# Hatch2023Trophy_1.net
KiCad netlist of a schematic drawn in EAGLE
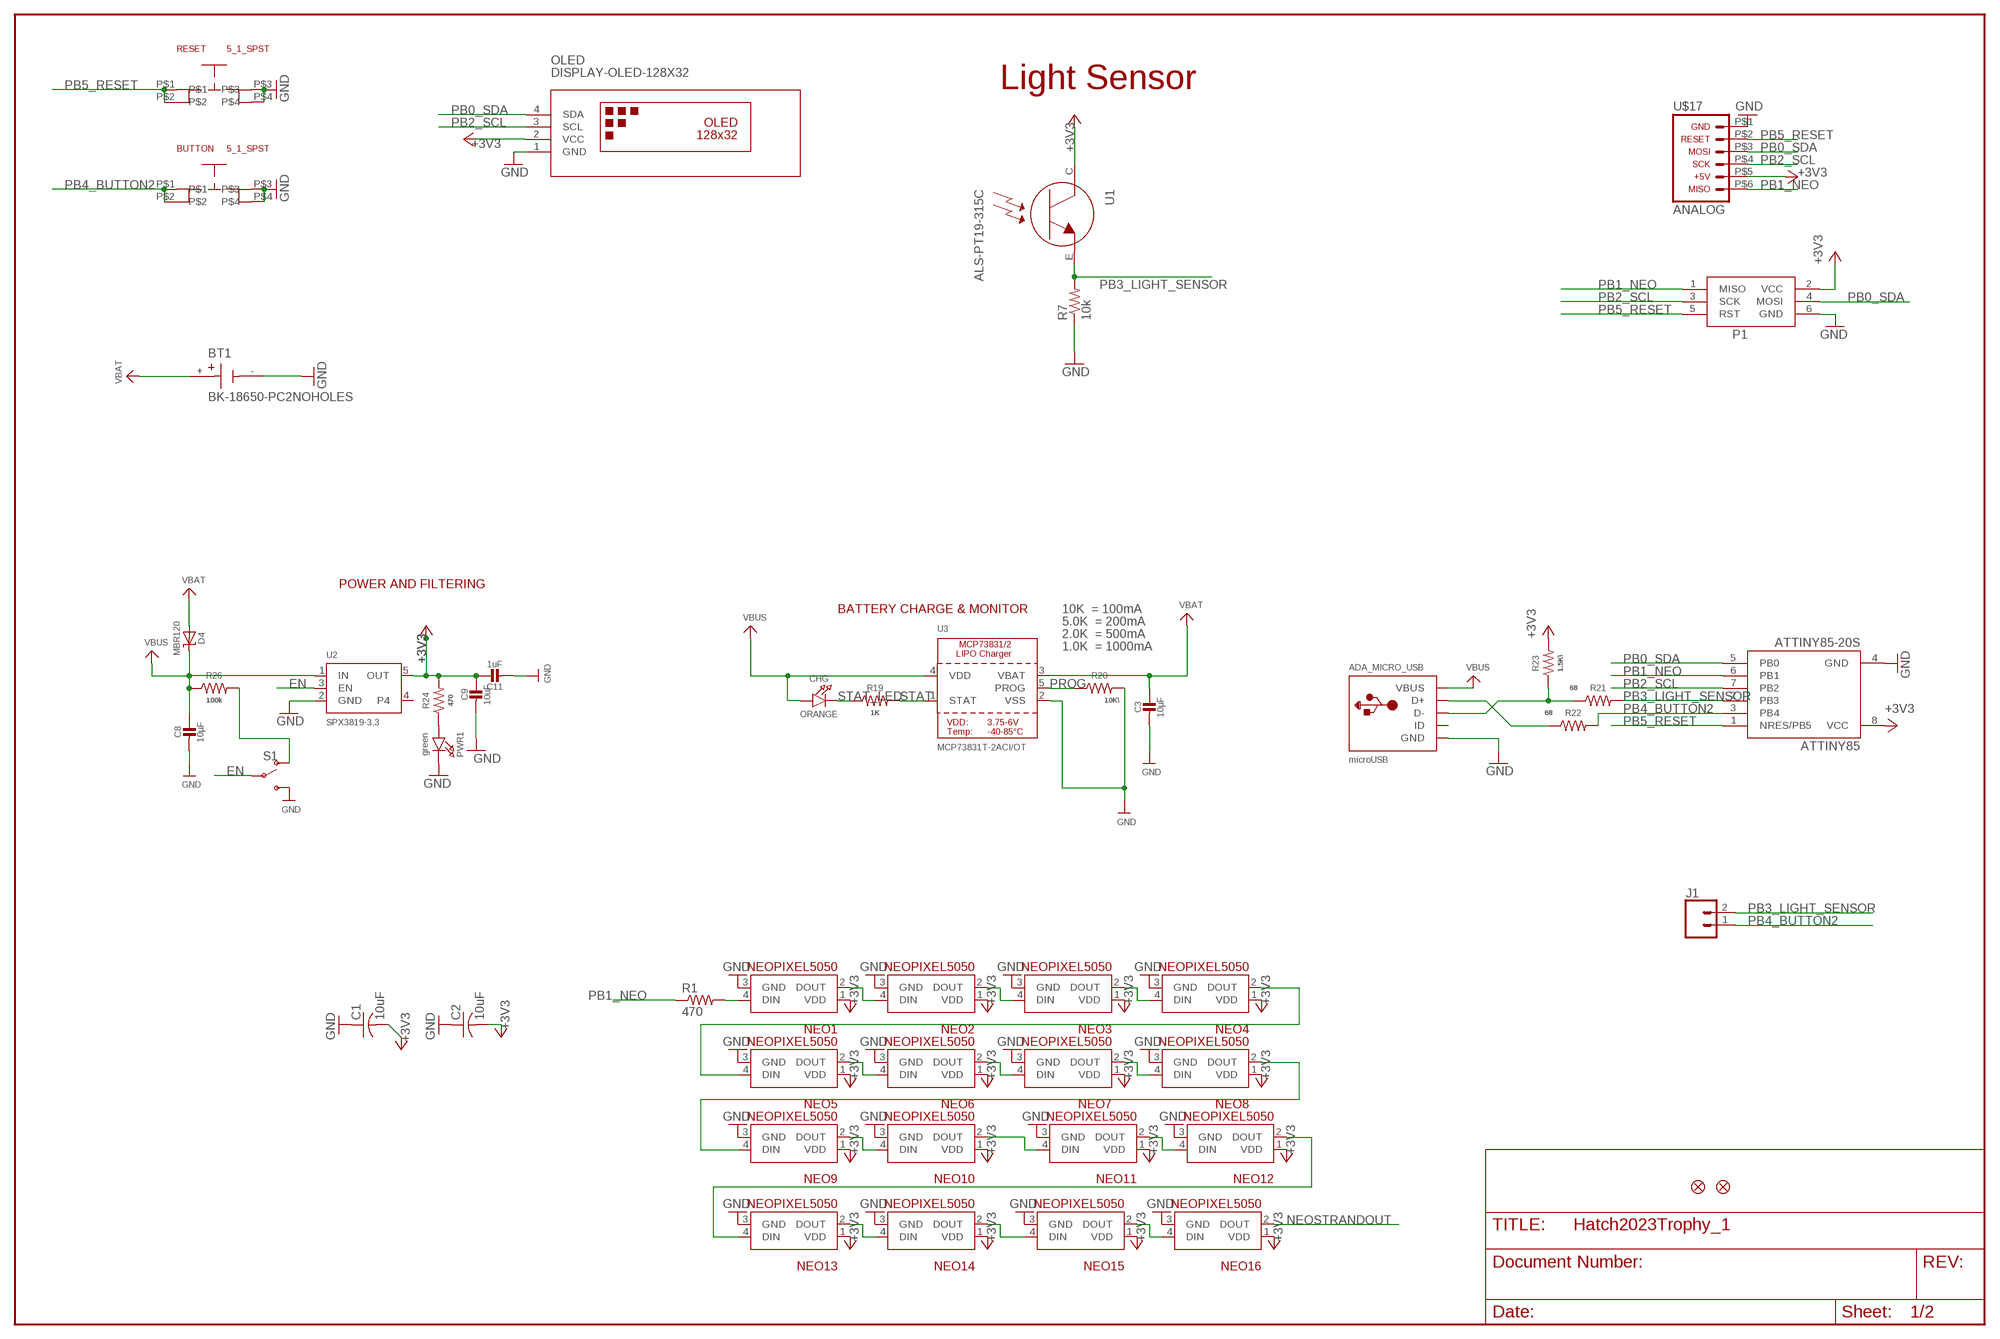
[diagram p0: schematic, sheet 1]

(export (version "E")
  (design (tool "Eeschema 10.0.6"))
  (components
    (comp (ref "ADA_MICRO_USB")
      (value "microUSB")
      (footprint "eagle-import:4UCONN_20329_V2")
      (libsource (lib "eagle-import") (part "USB_MICRO_20329_V2"))
    )
    (comp (ref "ATTINY85")
      (value "ATTINY85-20S")
      (footprint "eagle-import:SOIC8_EIAJ_208MIL")
      (libsource (lib "eagle-import") (part "ATTINY85S-20"))
    )
    (comp (ref "BT1")
      (value "BK-18650-PC2NOHOLES")
      (footprint "eagle-import:BAT_BK-18650-PC2_NOHOLES")
      (libsource (lib "eagle-import") (part "BK-18650-PC2NOHOLES"))
    )
    (comp (ref "BUTTON")
      (value "5_1_SPST")
      (footprint "eagle-import:5_1_SPST")
      (libsource (lib "eagle-import") (part "5_1_SPST"))
    )
    (comp (ref "C1")
      (value "10uF")
      (footprint "eagle-import:C0805")
      (libsource (lib "eagle-import") (part "C-USC0805"))
    )
    (comp (ref "C2")
      (value "10uF")
      (footprint "eagle-import:C0805")
      (libsource (lib "eagle-import") (part "C-USC0805"))
    )
    (comp (ref "C3")
      (value "10µF")
      (footprint "eagle-import:0805-NO@1")
      (libsource (lib "eagle-import") (part "CAP_CERAMIC0805-NOOUTLINE"))
    )
    (comp (ref "C8")
      (value "10µF")
      (footprint "eagle-import:0805-NO@1")
      (libsource (lib "eagle-import") (part "CAP_CERAMIC0805-NOOUTLINE"))
    )
    (comp (ref "C9")
      (value "10uF")
      (footprint "eagle-import:0805-NO@1")
      (libsource (lib "eagle-import") (part "CAP_CERAMIC0805-NOOUTLINE"))
    )
    (comp (ref "C11")
      (value "1uF")
      (footprint "eagle-import:0805-NO@1")
      (libsource (lib "eagle-import") (part "CAP_CERAMIC0805-NOOUTLINE"))
    )
    (comp (ref "CHG")
      (value "ORANGE")
      (footprint "eagle-import:CHIPLED_0805_NOOUTLINE")
      (libsource (lib "eagle-import") (part "LED0805_NOOUTLINE"))
    )
    (comp (ref "D4")
      (value "MBR120")
      (footprint "eagle-import:SOD-123")
      (libsource (lib "eagle-import") (part "DIODE-SCHOTTKYSOD-123"))
    )
    (comp (ref "J1")
      (value "CONN_02")
      (footprint "eagle-import:1X02")
      (libsource (lib "eagle-import") (part "CONN_02"))
    )
    (comp (ref "NEO1")
      (value "NEOPIXEL5050")
      (footprint "eagle-import:NEOPIXEL5050")
      (libsource (lib "eagle-import") (part "NEOPIXEL5050"))
    )
    (comp (ref "NEO2")
      (value "NEOPIXEL5050")
      (footprint "eagle-import:NEOPIXEL5050")
      (libsource (lib "eagle-import") (part "NEOPIXEL5050"))
    )
    (comp (ref "NEO3")
      (value "NEOPIXEL5050")
      (footprint "eagle-import:NEOPIXEL5050")
      (libsource (lib "eagle-import") (part "NEOPIXEL5050"))
    )
    (comp (ref "NEO4")
      (value "NEOPIXEL5050")
      (footprint "eagle-import:NEOPIXEL5050")
      (libsource (lib "eagle-import") (part "NEOPIXEL5050"))
    )
    (comp (ref "NEO5")
      (value "NEOPIXEL5050")
      (footprint "eagle-import:NEOPIXEL5050")
      (libsource (lib "eagle-import") (part "NEOPIXEL5050"))
    )
    (comp (ref "NEO6")
      (value "NEOPIXEL5050")
      (footprint "eagle-import:NEOPIXEL5050")
      (libsource (lib "eagle-import") (part "NEOPIXEL5050"))
    )
    (comp (ref "NEO7")
      (value "NEOPIXEL5050")
      (footprint "eagle-import:NEOPIXEL5050")
      (libsource (lib "eagle-import") (part "NEOPIXEL5050"))
    )
    (comp (ref "NEO8")
      (value "NEOPIXEL5050")
      (footprint "eagle-import:NEOPIXEL5050")
      (libsource (lib "eagle-import") (part "NEOPIXEL5050"))
    )
    (comp (ref "NEO9")
      (value "NEOPIXEL5050")
      (footprint "eagle-import:NEOPIXEL5050")
      (libsource (lib "eagle-import") (part "NEOPIXEL5050"))
    )
    (comp (ref "NEO10")
      (value "NEOPIXEL5050")
      (footprint "eagle-import:NEOPIXEL5050")
      (libsource (lib "eagle-import") (part "NEOPIXEL5050"))
    )
    (comp (ref "NEO11")
      (value "NEOPIXEL5050")
      (footprint "eagle-import:NEOPIXEL5050")
      (libsource (lib "eagle-import") (part "NEOPIXEL5050"))
    )
    (comp (ref "NEO12")
      (value "NEOPIXEL5050")
      (footprint "eagle-import:NEOPIXEL5050")
      (libsource (lib "eagle-import") (part "NEOPIXEL5050"))
    )
    (comp (ref "NEO13")
      (value "NEOPIXEL5050")
      (footprint "eagle-import:NEOPIXEL5050")
      (libsource (lib "eagle-import") (part "NEOPIXEL5050"))
    )
    (comp (ref "NEO14")
      (value "NEOPIXEL5050")
      (footprint "eagle-import:NEOPIXEL5050")
      (libsource (lib "eagle-import") (part "NEOPIXEL5050"))
    )
    (comp (ref "NEO15")
      (value "NEOPIXEL5050")
      (footprint "eagle-import:NEOPIXEL5050")
      (libsource (lib "eagle-import") (part "NEOPIXEL5050"))
    )
    (comp (ref "NEO16")
      (value "NEOPIXEL5050")
      (footprint "eagle-import:NEOPIXEL5050")
      (libsource (lib "eagle-import") (part "NEOPIXEL5050"))
    )
    (comp (ref "OLED")
      (value "DISPLAY-OLED-128X32")
      (footprint "eagle-import:DISPLAY-OLED-128X32")
      (libsource (lib "eagle-import") (part "DISPLAY-OLED-128X32"))
    )
    (comp (ref "P1")
      (value "AVRISP-6")
      (footprint "eagle-import:AVRISP")
      (libsource (lib "eagle-import") (part "AVRISP-6"))
    )
    (comp (ref "PWR1")
      (value "green")
      (footprint "eagle-import:CHIPLED_0805_NOOUTLINE")
      (libsource (lib "eagle-import") (part "LED0805_NOOUTLINE"))
    )
    (comp (ref "R1")
      (value "470")
      (footprint "eagle-import:R0805")
      (libsource (lib "eagle-import") (part "R-US_R0805"))
    )
    (comp (ref "R7")
      (value "10k")
      (footprint "eagle-import:R0805")
      (libsource (lib "eagle-import") (part "R-US_R0805"))
    )
    (comp (ref "R19")
      (value "1K")
      (footprint "eagle-import:R0805")
      (libsource (lib "eagle-import") (part "R-US_R0805"))
    )
    (comp (ref "R20")
      (value "10K\\")
      (footprint "eagle-import:R0805")
      (libsource (lib "eagle-import") (part "R-US_R0805"))
    )
    (comp (ref "R21")
      (value "68")
      (footprint "eagle-import:R0805")
      (libsource (lib "eagle-import") (part "R-US_R0805"))
    )
    (comp (ref "R22")
      (value "68")
      (footprint "eagle-import:R0805")
      (libsource (lib "eagle-import") (part "R-US_R0805"))
    )
    (comp (ref "R23")
      (value "1.5K\\")
      (footprint "eagle-import:R0805")
      (libsource (lib "eagle-import") (part "R-US_R0805"))
    )
    (comp (ref "R24")
      (value "470")
      (footprint "eagle-import:R0805")
      (libsource (lib "eagle-import") (part "R-US_R0805"))
    )
    (comp (ref "R26")
      (value "100k")
      (footprint "eagle-import:R0805")
      (libsource (lib "eagle-import") (part "R-US_R0805"))
    )
    (comp (ref "RESET")
      (value "5_1_SPST")
      (footprint "eagle-import:5_1_SPST")
      (libsource (lib "eagle-import") (part "5_1_SPST"))
    )
    (comp (ref "S1")
      (value "SWITCH-SPDT-SMD-AYZ0202")
      (footprint "eagle-import:SWITCH_DPDT_SMD_AYZ0202")
      (libsource (lib "eagle-import") (part "SWITCH-SPDT-SMD-AYZ0202"))
    )
    (comp (ref "U$17")
      (value "ICSP_FLATSMD_2X3")
      (footprint "eagle-import:CONN-SMD-2X3")
      (libsource (lib "eagle-import") (part "ICSP_FLATSMD_2X3"))
    )
    (comp (ref "U$34")
      (value "FIDUCIAL_1MM")
      (footprint "eagle-import:FIDUCIAL_1MM")
      (libsource (lib "eagle-import") (part "FIDUCIAL_1MM"))
    )
    (comp (ref "U$35")
      (value "FIDUCIAL_1MM")
      (footprint "eagle-import:FIDUCIAL_1MM")
      (libsource (lib "eagle-import") (part "FIDUCIAL_1MM"))
    )
    (comp (ref "U1")
      (value "ALS-PT19-315C")
      (footprint "eagle-import:ALS-PT19-315C")
      (libsource (lib "eagle-import") (part "LIGHT_ALS-PT19-315C"))
    )
    (comp (ref "U2")
      (value "SPX3819-3.3")
      (footprint "eagle-import:SOT23-5")
      (libsource (lib "eagle-import") (part "VREG_SOT23-5"))
    )
    (comp (ref "U3")
      (value "MCP73831T-2ACI/OT")
      (footprint "eagle-import:SOT23-5")
      (libsource (lib "eagle-import") (part "MCP73831/2"))
    )
  )
  (nets
    (net (code "1") (name "+3V3") (class "Default")
      (node (ref "ATTINY85") (pin "8") (pinfunction "VCC_8") (pintype "power_in"))
      (node (ref "C1") (pin "2") (pinfunction "2_2") (pintype "passive"))
      (node (ref "C11") (pin "1") (pinfunction "1_1") (pintype "passive"))
      (node (ref "C2") (pin "2") (pinfunction "2_2") (pintype "passive"))
      (node (ref "C9") (pin "1") (pinfunction "1_1") (pintype "passive"))
      (node (ref "NEO1") (pin "1") (pinfunction "VDD_1") (pintype "bidirectional"))
      (node (ref "NEO10") (pin "1") (pinfunction "VDD_1") (pintype "bidirectional"))
      (node (ref "NEO11") (pin "1") (pinfunction "VDD_1") (pintype "bidirectional"))
      (node (ref "NEO12") (pin "1") (pinfunction "VDD_1") (pintype "bidirectional"))
      (node (ref "NEO13") (pin "1") (pinfunction "VDD_1") (pintype "bidirectional"))
      (node (ref "NEO14") (pin "1") (pinfunction "VDD_1") (pintype "bidirectional"))
      (node (ref "NEO15") (pin "1") (pinfunction "VDD_1") (pintype "bidirectional"))
      (node (ref "NEO16") (pin "1") (pinfunction "VDD_1") (pintype "bidirectional"))
      (node (ref "NEO2") (pin "1") (pinfunction "VDD_1") (pintype "bidirectional"))
      (node (ref "NEO3") (pin "1") (pinfunction "VDD_1") (pintype "bidirectional"))
      (node (ref "NEO4") (pin "1") (pinfunction "VDD_1") (pintype "bidirectional"))
      (node (ref "NEO5") (pin "1") (pinfunction "VDD_1") (pintype "bidirectional"))
      (node (ref "NEO6") (pin "1") (pinfunction "VDD_1") (pintype "bidirectional"))
      (node (ref "NEO7") (pin "1") (pinfunction "VDD_1") (pintype "bidirectional"))
      (node (ref "NEO8") (pin "1") (pinfunction "VDD_1") (pintype "bidirectional"))
      (node (ref "NEO9") (pin "1") (pinfunction "VDD_1") (pintype "bidirectional"))
      (node (ref "OLED") (pin "2") (pinfunction "VCC_2") (pintype "power_in"))
      (node (ref "P1") (pin "2") (pinfunction "VCC_2") (pintype "power_in"))
      (node (ref "R23") (pin "2") (pinfunction "2_2") (pintype "passive"))
      (node (ref "R24") (pin "2") (pinfunction "2_2") (pintype "passive"))
      (node (ref "U$17") (pin "P$5") (pinfunction "5_P$5") (pintype "passive"))
      (node (ref "U1") (pin "C") (pinfunction "C_C") (pintype "bidirectional"))
      (node (ref "U2") (pin "5") (pinfunction "OUT_5") (pintype "power_in"))
    )
    (net (code "2") (name "EN") (class "Default")
      (node (ref "S1") (pin "2") (pinfunction "P_2") (pintype "passive"))
      (node (ref "U2") (pin "3") (pinfunction "EN_3") (pintype "input"))
    )
    (net (code "3") (name "GND") (class "Default")
      (node (ref "ADA_MICRO_USB") (pin "BASE@1") (pinfunction "GND_BASE@1") (pintype "power_in"))
      (node (ref "ADA_MICRO_USB") (pin "BASE@2") (pinfunction "GND_BASE@2") (pintype "power_in"))
      (node (ref "ADA_MICRO_USB") (pin "GND") (pinfunction "GND_GND") (pintype "power_in"))
      (node (ref "ADA_MICRO_USB") (pin "SPRT@1") (pinfunction "GND_SPRT@1") (pintype "power_in"))
      (node (ref "ADA_MICRO_USB") (pin "SPRT@2") (pinfunction "GND_SPRT@2") (pintype "power_in"))
      (node (ref "ADA_MICRO_USB") (pin "SPRT@3") (pinfunction "GND_SPRT@3") (pintype "power_in"))
      (node (ref "ADA_MICRO_USB") (pin "SPRT@4") (pinfunction "GND_SPRT@4") (pintype "power_in"))
      (node (ref "ATTINY85") (pin "4") (pinfunction "GND_4") (pintype "power_in"))
      (node (ref "BT1") (pin "-") (pinfunction "-_-") (pintype "passive"))
      (node (ref "BUTTON") (pin "P$3") (pinfunction "P$3_P$3") (pintype "bidirectional"))
      (node (ref "BUTTON") (pin "P$4") (pinfunction "P$4_P$4") (pintype "bidirectional"))
      (node (ref "C1") (pin "1") (pinfunction "1_1") (pintype "passive"))
      (node (ref "C11") (pin "2") (pinfunction "2_2") (pintype "passive"))
      (node (ref "C2") (pin "1") (pinfunction "1_1") (pintype "passive"))
      (node (ref "C3") (pin "2") (pinfunction "2_2") (pintype "passive"))
      (node (ref "C8") (pin "2") (pinfunction "2_2") (pintype "passive"))
      (node (ref "C9") (pin "2") (pinfunction "2_2") (pintype "passive"))
      (node (ref "NEO1") (pin "3") (pinfunction "GND_3") (pintype "bidirectional"))
      (node (ref "NEO10") (pin "3") (pinfunction "GND_3") (pintype "bidirectional"))
      (node (ref "NEO11") (pin "3") (pinfunction "GND_3") (pintype "bidirectional"))
      (node (ref "NEO12") (pin "3") (pinfunction "GND_3") (pintype "bidirectional"))
      (node (ref "NEO13") (pin "3") (pinfunction "GND_3") (pintype "bidirectional"))
      (node (ref "NEO14") (pin "3") (pinfunction "GND_3") (pintype "bidirectional"))
      (node (ref "NEO15") (pin "3") (pinfunction "GND_3") (pintype "bidirectional"))
      (node (ref "NEO16") (pin "3") (pinfunction "GND_3") (pintype "bidirectional"))
      (node (ref "NEO2") (pin "3") (pinfunction "GND_3") (pintype "bidirectional"))
      (node (ref "NEO3") (pin "3") (pinfunction "GND_3") (pintype "bidirectional"))
      (node (ref "NEO4") (pin "3") (pinfunction "GND_3") (pintype "bidirectional"))
      (node (ref "NEO5") (pin "3") (pinfunction "GND_3") (pintype "bidirectional"))
      (node (ref "NEO6") (pin "3") (pinfunction "GND_3") (pintype "bidirectional"))
      (node (ref "NEO7") (pin "3") (pinfunction "GND_3") (pintype "bidirectional"))
      (node (ref "NEO8") (pin "3") (pinfunction "GND_3") (pintype "bidirectional"))
      (node (ref "NEO9") (pin "3") (pinfunction "GND_3") (pintype "bidirectional"))
      (node (ref "OLED") (pin "1") (pinfunction "GND_1") (pintype "power_in"))
      (node (ref "P1") (pin "6") (pinfunction "GND_6") (pintype "power_in"))
      (node (ref "PWR1") (pin "C") (pinfunction "C_C") (pintype "passive"))
      (node (ref "R20") (pin "2") (pinfunction "2_2") (pintype "passive"))
      (node (ref "R7") (pin "1") (pinfunction "1_1") (pintype "passive"))
      (node (ref "RESET") (pin "P$3") (pinfunction "P$3_P$3") (pintype "bidirectional"))
      (node (ref "RESET") (pin "P$4") (pinfunction "P$4_P$4") (pintype "bidirectional"))
      (node (ref "S1") (pin "3") (pinfunction "S_3") (pintype "passive"))
      (node (ref "U$17") (pin "P$1") (pinfunction "1_P$1") (pintype "passive"))
      (node (ref "U2") (pin "2") (pinfunction "GND_2") (pintype "power_in"))
      (node (ref "U3") (pin "2") (pinfunction "VSS_2") (pintype "power_in"))
    )
    (net (code "4") (name "NEOSTRANDOUT") (class "Default")
      (node (ref "NEO16") (pin "2") (pinfunction "DOUT_2") (pintype "bidirectional"))
    )
    (net (code "5") (name "Net-(ADA_MICRO_USB-PadD+)") (class "Default")
      (node (ref "ADA_MICRO_USB") (pin "D+") (pinfunction "D+_D+") (pintype "bidirectional"))
      (node (ref "R22") (pin "1") (pinfunction "1_1") (pintype "passive"))
    )
    (net (code "6") (name "Net-(ADA_MICRO_USB-PadD-)") (class "Default")
      (node (ref "ADA_MICRO_USB") (pin "D-") (pinfunction "D-_D-") (pintype "bidirectional"))
      (node (ref "R21") (pin "1") (pinfunction "1_1") (pintype "passive"))
      (node (ref "R23") (pin "1") (pinfunction "1_1") (pintype "passive"))
    )
    (net (code "7") (name "Net-(NEO1-DIN)") (class "Default")
      (node (ref "NEO1") (pin "4") (pinfunction "DIN_4") (pintype "bidirectional"))
      (node (ref "R1") (pin "2") (pinfunction "2_2") (pintype "passive"))
    )
    (net (code "8") (name "Net-(NEO1-DOUT)") (class "Default")
      (node (ref "NEO1") (pin "2") (pinfunction "DOUT_2") (pintype "bidirectional"))
      (node (ref "NEO2") (pin "4") (pinfunction "DIN_4") (pintype "bidirectional"))
    )
    (net (code "9") (name "Net-(NEO2-DOUT)") (class "Default")
      (node (ref "NEO2") (pin "2") (pinfunction "DOUT_2") (pintype "bidirectional"))
      (node (ref "NEO3") (pin "4") (pinfunction "DIN_4") (pintype "bidirectional"))
    )
    (net (code "10") (name "Net-(NEO3-DOUT)") (class "Default")
      (node (ref "NEO3") (pin "2") (pinfunction "DOUT_2") (pintype "bidirectional"))
      (node (ref "NEO4") (pin "4") (pinfunction "DIN_4") (pintype "bidirectional"))
    )
    (net (code "11") (name "Net-(NEO4-DOUT)") (class "Default")
      (node (ref "NEO4") (pin "2") (pinfunction "DOUT_2") (pintype "bidirectional"))
      (node (ref "NEO5") (pin "4") (pinfunction "DIN_4") (pintype "bidirectional"))
    )
    (net (code "12") (name "Net-(NEO5-DOUT)") (class "Default")
      (node (ref "NEO5") (pin "2") (pinfunction "DOUT_2") (pintype "bidirectional"))
      (node (ref "NEO6") (pin "4") (pinfunction "DIN_4") (pintype "bidirectional"))
    )
    (net (code "13") (name "Net-(NEO6-DOUT)") (class "Default")
      (node (ref "NEO6") (pin "2") (pinfunction "DOUT_2") (pintype "bidirectional"))
      (node (ref "NEO7") (pin "4") (pinfunction "DIN_4") (pintype "bidirectional"))
    )
    (net (code "14") (name "Net-(NEO7-DOUT)") (class "Default")
      (node (ref "NEO7") (pin "2") (pinfunction "DOUT_2") (pintype "bidirectional"))
      (node (ref "NEO8") (pin "4") (pinfunction "DIN_4") (pintype "bidirectional"))
    )
    (net (code "15") (name "Net-(NEO8-DOUT)") (class "Default")
      (node (ref "NEO8") (pin "2") (pinfunction "DOUT_2") (pintype "bidirectional"))
      (node (ref "NEO9") (pin "4") (pinfunction "DIN_4") (pintype "bidirectional"))
    )
    (net (code "16") (name "Net-(NEO10-DIN)") (class "Default")
      (node (ref "NEO10") (pin "4") (pinfunction "DIN_4") (pintype "bidirectional"))
      (node (ref "NEO9") (pin "2") (pinfunction "DOUT_2") (pintype "bidirectional"))
    )
    (net (code "17") (name "Net-(NEO10-DOUT)") (class "Default")
      (node (ref "NEO10") (pin "2") (pinfunction "DOUT_2") (pintype "bidirectional"))
      (node (ref "NEO11") (pin "4") (pinfunction "DIN_4") (pintype "bidirectional"))
    )
    (net (code "18") (name "Net-(NEO11-DOUT)") (class "Default")
      (node (ref "NEO11") (pin "2") (pinfunction "DOUT_2") (pintype "bidirectional"))
      (node (ref "NEO12") (pin "4") (pinfunction "DIN_4") (pintype "bidirectional"))
    )
    (net (code "19") (name "Net-(NEO12-DOUT)") (class "Default")
      (node (ref "NEO12") (pin "2") (pinfunction "DOUT_2") (pintype "bidirectional"))
      (node (ref "NEO13") (pin "4") (pinfunction "DIN_4") (pintype "bidirectional"))
    )
    (net (code "20") (name "Net-(NEO13-DOUT)") (class "Default")
      (node (ref "NEO13") (pin "2") (pinfunction "DOUT_2") (pintype "bidirectional"))
      (node (ref "NEO14") (pin "4") (pinfunction "DIN_4") (pintype "bidirectional"))
    )
    (net (code "21") (name "Net-(NEO14-DOUT)") (class "Default")
      (node (ref "NEO14") (pin "2") (pinfunction "DOUT_2") (pintype "bidirectional"))
      (node (ref "NEO15") (pin "4") (pinfunction "DIN_4") (pintype "bidirectional"))
    )
    (net (code "22") (name "Net-(NEO15-DOUT)") (class "Default")
      (node (ref "NEO15") (pin "2") (pinfunction "DOUT_2") (pintype "bidirectional"))
      (node (ref "NEO16") (pin "4") (pinfunction "DIN_4") (pintype "bidirectional"))
    )
    (net (code "23") (name "Net-(PWR1-PadA)") (class "Default")
      (node (ref "PWR1") (pin "A") (pinfunction "A_A") (pintype "passive"))
      (node (ref "R24") (pin "1") (pinfunction "1_1") (pintype "passive"))
    )
    (net (code "24") (name "Net-(S1-O)") (class "Default")
      (node (ref "R26") (pin "2") (pinfunction "2_2") (pintype "passive"))
      (node (ref "S1") (pin "1") (pinfunction "O_1") (pintype "passive"))
    )
    (net (code "25") (name "PB0_SDA") (class "Default")
      (node (ref "ATTINY85") (pin "5") (pinfunction "PB0_5") (pintype "bidirectional"))
      (node (ref "OLED") (pin "4") (pinfunction "SDA_4") (pintype "bidirectional"))
      (node (ref "P1") (pin "4") (pinfunction "MOSI_4") (pintype "output"))
      (node (ref "U$17") (pin "P$3") (pinfunction "3_P$3") (pintype "passive"))
    )
    (net (code "26") (name "PB1_NEO") (class "Default")
      (node (ref "ATTINY85") (pin "6") (pinfunction "PB1_6") (pintype "bidirectional"))
      (node (ref "P1") (pin "1") (pinfunction "MISO_1") (pintype "input"))
      (node (ref "R1") (pin "1") (pinfunction "1_1") (pintype "passive"))
      (node (ref "U$17") (pin "P$6") (pinfunction "6_P$6") (pintype "passive"))
    )
    (net (code "27") (name "PB2_SCL") (class "Default")
      (node (ref "ATTINY85") (pin "7") (pinfunction "PB2_7") (pintype "bidirectional"))
      (node (ref "OLED") (pin "3") (pinfunction "SCL_3") (pintype "bidirectional"))
      (node (ref "P1") (pin "3") (pinfunction "SCK_3") (pintype "output"))
      (node (ref "U$17") (pin "P$4") (pinfunction "4_P$4") (pintype "passive"))
    )
    (net (code "28") (name "PB3_LIGHT_SENSOR") (class "Default")
      (node (ref "ATTINY85") (pin "2") (pinfunction "PB3_2") (pintype "bidirectional"))
      (node (ref "J1") (pin "2") (pinfunction "2_2") (pintype "passive"))
      (node (ref "R21") (pin "2") (pinfunction "2_2") (pintype "passive"))
      (node (ref "R7") (pin "2") (pinfunction "2_2") (pintype "passive"))
      (node (ref "U1") (pin "E") (pinfunction "E_E") (pintype "bidirectional"))
    )
    (net (code "29") (name "PB4_BUTTON2") (class "Default")
      (node (ref "ATTINY85") (pin "3") (pinfunction "PB4_3") (pintype "bidirectional"))
      (node (ref "BUTTON") (pin "P$1") (pinfunction "P$1_P$1") (pintype "bidirectional"))
      (node (ref "BUTTON") (pin "P$2") (pinfunction "P$2_P$2") (pintype "bidirectional"))
      (node (ref "J1") (pin "1") (pinfunction "1_1") (pintype "passive"))
      (node (ref "R22") (pin "2") (pinfunction "2_2") (pintype "passive"))
    )
    (net (code "30") (name "PB5_RESET") (class "Default")
      (node (ref "ATTINY85") (pin "1") (pinfunction "NRES/PB5_1") (pintype "bidirectional"))
      (node (ref "P1") (pin "5") (pinfunction "RST_5") (pintype "output"))
      (node (ref "RESET") (pin "P$1") (pinfunction "P$1_P$1") (pintype "bidirectional"))
      (node (ref "RESET") (pin "P$2") (pinfunction "P$2_P$2") (pintype "bidirectional"))
      (node (ref "U$17") (pin "P$2") (pinfunction "2_P$2") (pintype "passive"))
    )
    (net (code "31") (name "PROG") (class "Default")
      (node (ref "R20") (pin "1") (pinfunction "1_1") (pintype "passive"))
      (node (ref "U3") (pin "5") (pinfunction "PROG_5") (pintype "input"))
    )
    (net (code "32") (name "STAT") (class "Default")
      (node (ref "R19") (pin "2") (pinfunction "2_2") (pintype "passive"))
      (node (ref "U3") (pin "1") (pinfunction "STAT_1") (pintype "output"))
    )
    (net (code "33") (name "STAT_LED") (class "Default")
      (node (ref "CHG") (pin "C") (pinfunction "C_C") (pintype "passive"))
      (node (ref "R19") (pin "1") (pinfunction "1_1") (pintype "passive"))
    )
    (net (code "34") (name "VBAT") (class "Default")
      (node (ref "BT1") (pin "+") (pinfunction "+_+") (pintype "passive"))
      (node (ref "C3") (pin "1") (pinfunction "1_1") (pintype "passive"))
      (node (ref "D4") (pin "A") (pinfunction "A_A") (pintype "passive"))
      (node (ref "U3") (pin "3") (pinfunction "VBAT_3") (pintype "power_in"))
    )
    (net (code "35") (name "VBUS") (class "Default")
      (node (ref "ADA_MICRO_USB") (pin "VBUS") (pinfunction "VBUS_VBUS") (pintype "power_in"))
      (node (ref "C8") (pin "1") (pinfunction "1_1") (pintype "passive"))
      (node (ref "CHG") (pin "A") (pinfunction "A_A") (pintype "passive"))
      (node (ref "D4") (pin "C") (pinfunction "C_C") (pintype "passive"))
      (node (ref "R26") (pin "1") (pinfunction "1_1") (pintype "passive"))
      (node (ref "U2") (pin "1") (pinfunction "IN_1") (pintype "power_in"))
      (node (ref "U3") (pin "4") (pinfunction "VDD_4") (pintype "power_in"))
    )
    (net (code "36") (name "unconnected-(ADA_MICRO_USB-PadID)") (class "Default")
      (node (ref "ADA_MICRO_USB") (pin "ID") (pinfunction "ID_ID") (pintype "bidirectional"))
    )
    (net (code "37") (name "unconnected-(U2-P4-Pad4)") (class "Default")
      (node (ref "U2") (pin "4") (pinfunction "P4_4") (pintype "bidirectional"))
    )
  )
)
